# POWER.net
KiCad netlist of a schematic drawn in Altium Designer
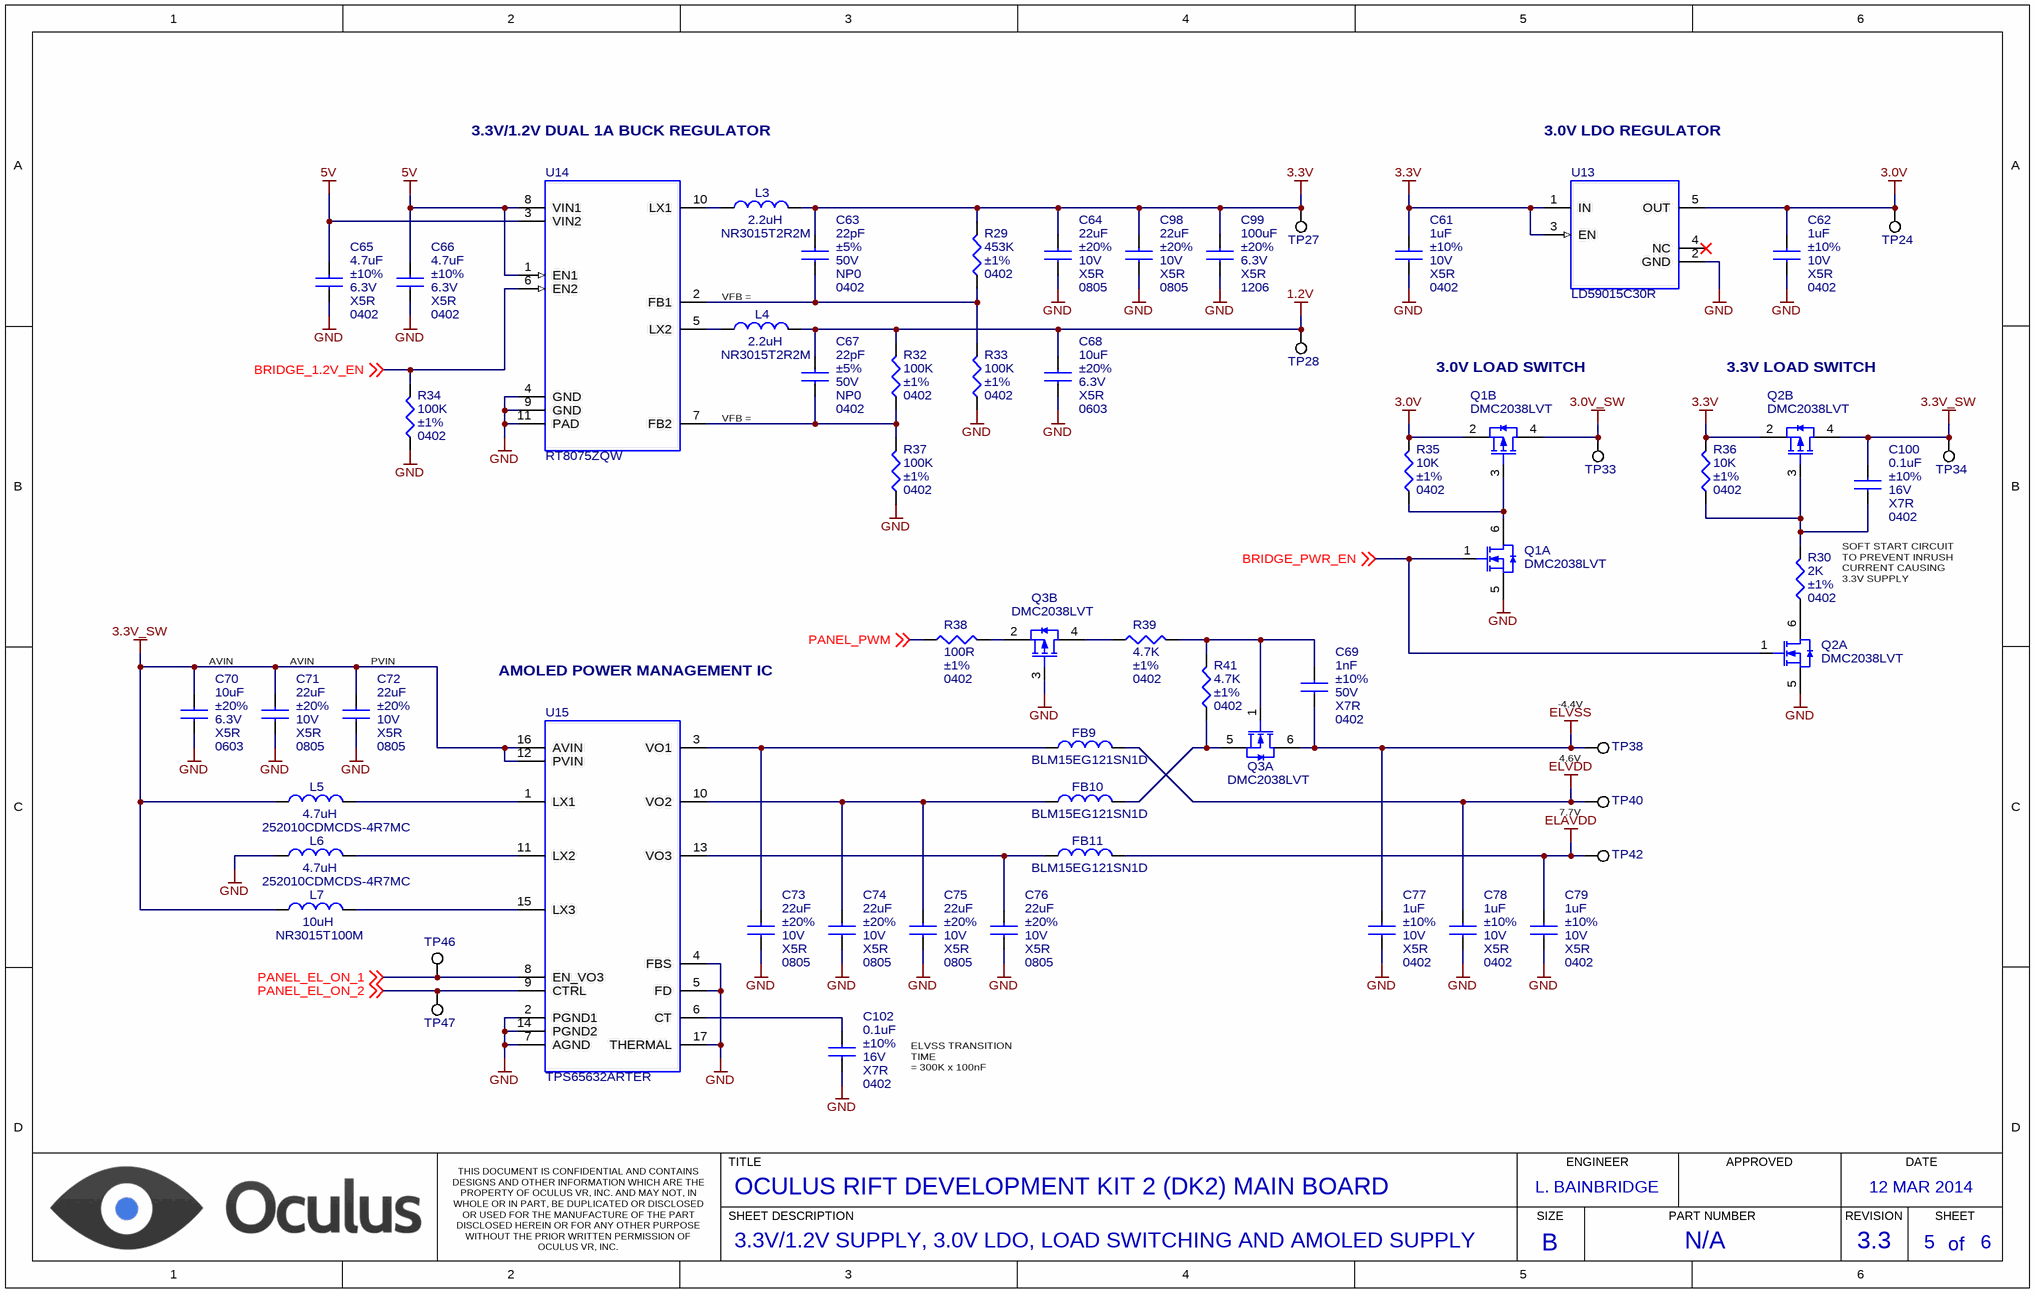
[diagram p0: POWER.SchDoc]

(export (version "E")
  (design (tool "Eeschema 10.0.6"))
  (components
    (comp (ref "C61")
      (value "1uF")
      (footprint "CAP_CERAMIC_0402")
      (description "CAP, CERAMIC, 1uF, ±10%, 10V, X5R, 0402")
      (fields
        (field (name "MANUFACTURER") "MURATA ELECTRONICS")
        (field (name "PART NUMBER") "GRM155R61A105KE15D")
        (field (name "TOLERANCE") "±10%")
        (field (name "VOLTAGE") "10V")
        (field (name "DIELECTRIC") "X5R")
        (field (name "PACKAGE") "0402")
      )
      (libsource (lib "DK2") (part "CAP, CERAMIC"))
    )
    (comp (ref "C62")
      (value "1uF")
      (footprint "CAP_CERAMIC_0402")
      (description "CAP, CERAMIC, 1uF, ±10%, 10V, X5R, 0402")
      (fields
        (field (name "MANUFACTURER") "MURATA ELECTRONICS")
        (field (name "PART NUMBER") "GRM155R61A105KE15D")
        (field (name "TOLERANCE") "±10%")
        (field (name "VOLTAGE") "10V")
        (field (name "DIELECTRIC") "X5R")
        (field (name "PACKAGE") "0402")
      )
      (libsource (lib "DK2") (part "CAP, CERAMIC"))
    )
    (comp (ref "C63")
      (value "22pF")
      (footprint "CAP_CERAMIC_0402")
      (description "CAP, CERAMIC, 22pF, ±5%, 50V, NP0, 0402")
      (fields
        (field (name "MANUFACTURER") "MURATA ELECTRONICS")
        (field (name "PART NUMBER") "GRM1535C1H220JDD5D")
        (field (name "TOLERANCE") "±5%")
        (field (name "VOLTAGE") "50V")
        (field (name "DIELECTRIC") "NP0")
        (field (name "PACKAGE") "0402")
      )
      (libsource (lib "DK2") (part "CAP, CERAMIC"))
    )
    (comp (ref "C64")
      (value "22uF")
      (footprint "CAP_CERAMIC_0805")
      (description "CAP, CERAMIC, 22uF, ±20%, 10V, X5R, 0805")
      (fields
        (field (name "MANUFACTURER") "SAMSUNG")
        (field (name "PART NUMBER") "CL21A226MPQNNNE")
        (field (name "TOLERANCE") "±20%")
        (field (name "VOLTAGE") "10V")
        (field (name "DIELECTRIC") "X5R")
        (field (name "PACKAGE") "0805")
      )
      (libsource (lib "DK2") (part "CAP, CERAMIC"))
    )
    (comp (ref "C65")
      (value "4.7uF")
      (footprint "CAP_CERAMIC_0402")
      (description "CAP, CERAMIC, 4.7uF, ±10%, 6.3V, X5R, 0402")
      (fields
        (field (name "MANUFACTURER") "TDK CORPORATION")
        (field (name "PART NUMBER") "C1005X5R0J475K")
        (field (name "TOLERANCE") "±10%")
        (field (name "VOLTAGE") "6.3V")
        (field (name "DIELECTRIC") "X5R")
        (field (name "PACKAGE") "0402")
      )
      (libsource (lib "DK2") (part "CAP, CERAMIC"))
    )
    (comp (ref "C66")
      (value "4.7uF")
      (footprint "CAP_CERAMIC_0402")
      (description "CAP, CERAMIC, 4.7uF, ±10%, 6.3V, X5R, 0402")
      (fields
        (field (name "MANUFACTURER") "TDK CORPORATION")
        (field (name "PART NUMBER") "C1005X5R0J475K")
        (field (name "TOLERANCE") "±10%")
        (field (name "VOLTAGE") "6.3V")
        (field (name "DIELECTRIC") "X5R")
        (field (name "PACKAGE") "0402")
      )
      (libsource (lib "DK2") (part "CAP, CERAMIC"))
    )
    (comp (ref "C67")
      (value "22pF")
      (footprint "CAP_CERAMIC_0402")
      (description "CAP, CERAMIC, 22pF, ±5%, 50V, NP0, 0402")
      (fields
        (field (name "MANUFACTURER") "MURATA ELECTRONICS")
        (field (name "PART NUMBER") "GRM1535C1H220JDD5D")
        (field (name "TOLERANCE") "±5%")
        (field (name "VOLTAGE") "50V")
        (field (name "DIELECTRIC") "NP0")
        (field (name "PACKAGE") "0402")
      )
      (libsource (lib "DK2") (part "CAP, CERAMIC"))
    )
    (comp (ref "C68")
      (value "10uF")
      (footprint "CAP_CERAMIC_0603")
      (description "CAP, CERAMIC, 10uF, ±20%, 6.3V, X5R, 0603")
      (fields
        (field (name "MANUFACTURER") "MURATA ELECTRONICS")
        (field (name "PART NUMBER") "GRM188R60J106ME47D")
        (field (name "TOLERANCE") "±20%")
        (field (name "VOLTAGE") "6.3V")
        (field (name "DIELECTRIC") "X5R")
        (field (name "PACKAGE") "0603")
      )
      (libsource (lib "DK2") (part "CAP, CERAMIC"))
    )
    (comp (ref "C69")
      (value "1nF")
      (footprint "CAP_CERAMIC_0402")
      (description "CAP, CERAMIC, 1nF, ±10%, 50V, X7R, 0402")
      (fields
        (field (name "MANUFACTURER") "MURATA ELECTRONICS")
        (field (name "PART NUMBER") "GRM155R71H102KA01D")
        (field (name "TOLERANCE") "±10%")
        (field (name "VOLTAGE") "50V")
        (field (name "DIELECTRIC") "X7R")
        (field (name "PACKAGE") "0402")
      )
      (libsource (lib "DK2") (part "CAP, CERAMIC"))
    )
    (comp (ref "C70")
      (value "10uF")
      (footprint "CAP_CERAMIC_0603")
      (description "CAP, CERAMIC, 10uF, ±20%, 6.3V, X5R, 0603")
      (fields
        (field (name "MANUFACTURER") "MURATA ELECTRONICS")
        (field (name "PART NUMBER") "GRM188R60J106ME47D")
        (field (name "TOLERANCE") "±20%")
        (field (name "VOLTAGE") "6.3V")
        (field (name "DIELECTRIC") "X5R")
        (field (name "PACKAGE") "0603")
      )
      (libsource (lib "DK2") (part "CAP, CERAMIC"))
    )
    (comp (ref "C71")
      (value "22uF")
      (footprint "CAP_CERAMIC_0805")
      (description "CAP, CERAMIC, 22uF, ±20%, 10V, X5R, 0805")
      (fields
        (field (name "MANUFACTURER") "SAMSUNG")
        (field (name "PART NUMBER") "CL21A226MPQNNNE")
        (field (name "TOLERANCE") "±20%")
        (field (name "VOLTAGE") "10V")
        (field (name "DIELECTRIC") "X5R")
        (field (name "PACKAGE") "0805")
      )
      (libsource (lib "DK2") (part "CAP, CERAMIC"))
    )
    (comp (ref "C72")
      (value "22uF")
      (footprint "CAP_CERAMIC_0805")
      (description "CAP, CERAMIC, 22uF, ±20%, 10V, X5R, 0805")
      (fields
        (field (name "MANUFACTURER") "SAMSUNG")
        (field (name "PART NUMBER") "CL21A226MPQNNNE")
        (field (name "TOLERANCE") "±20%")
        (field (name "VOLTAGE") "10V")
        (field (name "DIELECTRIC") "X5R")
        (field (name "PACKAGE") "0805")
      )
      (libsource (lib "DK2") (part "CAP, CERAMIC"))
    )
    (comp (ref "C73")
      (value "22uF")
      (footprint "CAP_CERAMIC_0805")
      (description "CAP, CERAMIC, 22uF, ±20%, 10V, X5R, 0805")
      (fields
        (field (name "MANUFACTURER") "SAMSUNG")
        (field (name "PART NUMBER") "CL21A226MPQNNNE")
        (field (name "TOLERANCE") "±20%")
        (field (name "VOLTAGE") "10V")
        (field (name "DIELECTRIC") "X5R")
        (field (name "PACKAGE") "0805")
      )
      (libsource (lib "DK2") (part "CAP, CERAMIC"))
    )
    (comp (ref "C74")
      (value "22uF")
      (footprint "CAP_CERAMIC_0805")
      (description "CAP, CERAMIC, 22uF, ±20%, 10V, X5R, 0805")
      (fields
        (field (name "MANUFACTURER") "SAMSUNG")
        (field (name "PART NUMBER") "CL21A226MPQNNNE")
        (field (name "TOLERANCE") "±20%")
        (field (name "VOLTAGE") "10V")
        (field (name "DIELECTRIC") "X5R")
        (field (name "PACKAGE") "0805")
      )
      (libsource (lib "DK2") (part "CAP, CERAMIC"))
    )
    (comp (ref "C75")
      (value "22uF")
      (footprint "CAP_CERAMIC_0805")
      (description "CAP, CERAMIC, 22uF, ±20%, 10V, X5R, 0805")
      (fields
        (field (name "MANUFACTURER") "SAMSUNG")
        (field (name "PART NUMBER") "CL21A226MPQNNNE")
        (field (name "TOLERANCE") "±20%")
        (field (name "VOLTAGE") "10V")
        (field (name "DIELECTRIC") "X5R")
        (field (name "PACKAGE") "0805")
      )
      (libsource (lib "DK2") (part "CAP, CERAMIC"))
    )
    (comp (ref "C76")
      (value "22uF")
      (footprint "CAP_CERAMIC_0805")
      (description "CAP, CERAMIC, 22uF, ±20%, 10V, X5R, 0805")
      (fields
        (field (name "MANUFACTURER") "SAMSUNG")
        (field (name "PART NUMBER") "CL21A226MPQNNNE")
        (field (name "TOLERANCE") "±20%")
        (field (name "VOLTAGE") "10V")
        (field (name "DIELECTRIC") "X5R")
        (field (name "PACKAGE") "0805")
      )
      (libsource (lib "DK2") (part "CAP, CERAMIC"))
    )
    (comp (ref "C77")
      (value "1uF")
      (footprint "CAP_CERAMIC_0402")
      (description "CAP, CERAMIC, 1uF, ±10%, 10V, X5R, 0402")
      (fields
        (field (name "MANUFACTURER") "MURATA ELECTRONICS")
        (field (name "PART NUMBER") "GRM155R61A105KE15D")
        (field (name "TOLERANCE") "±10%")
        (field (name "VOLTAGE") "10V")
        (field (name "DIELECTRIC") "X5R")
        (field (name "PACKAGE") "0402")
      )
      (libsource (lib "DK2") (part "CAP, CERAMIC"))
    )
    (comp (ref "C78")
      (value "1uF")
      (footprint "CAP_CERAMIC_0402")
      (description "CAP, CERAMIC, 1uF, ±10%, 10V, X5R, 0402")
      (fields
        (field (name "MANUFACTURER") "MURATA ELECTRONICS")
        (field (name "PART NUMBER") "GRM155R61A105KE15D")
        (field (name "TOLERANCE") "±10%")
        (field (name "VOLTAGE") "10V")
        (field (name "DIELECTRIC") "X5R")
        (field (name "PACKAGE") "0402")
      )
      (libsource (lib "DK2") (part "CAP, CERAMIC"))
    )
    (comp (ref "C79")
      (value "1uF")
      (footprint "CAP_CERAMIC_0402")
      (description "CAP, CERAMIC, 1uF, ±10%, 10V, X5R, 0402")
      (fields
        (field (name "MANUFACTURER") "MURATA ELECTRONICS")
        (field (name "PART NUMBER") "GRM155R61A105KE15D")
        (field (name "TOLERANCE") "±10%")
        (field (name "VOLTAGE") "10V")
        (field (name "DIELECTRIC") "X5R")
        (field (name "PACKAGE") "0402")
      )
      (libsource (lib "DK2") (part "CAP, CERAMIC"))
    )
    (comp (ref "C98")
      (value "22uF")
      (footprint "CAP_CERAMIC_0805")
      (description "CAP, CERAMIC, 22uF, ±20%, 10V, X5R, 0805")
      (fields
        (field (name "MANUFACTURER") "SAMSUNG")
        (field (name "PART NUMBER") "CL21A226MPQNNNE")
        (field (name "TOLERANCE") "±20%")
        (field (name "VOLTAGE") "10V")
        (field (name "DIELECTRIC") "X5R")
        (field (name "PACKAGE") "0805")
      )
      (libsource (lib "DK2") (part "CAP, CERAMIC"))
    )
    (comp (ref "C99")
      (value "100uF")
      (footprint "CAP_CERAMIC_1206")
      (description "CAP, CERAMIC, 100uF, ±20%, 6.3V, X5R, 1206")
      (fields
        (field (name "MANUFACTURER") "MURATA ELECTRONICS")
        (field (name "PART NUMBER") "GRM31CR60J107ME39K")
        (field (name "TOLERANCE") "±20%")
        (field (name "VOLTAGE") "6.3V")
        (field (name "DIELECTRIC") "X5R")
        (field (name "PACKAGE") "1206")
      )
      (libsource (lib "DK2") (part "CAP, CERAMIC"))
    )
    (comp (ref "C100")
      (value "0.1uF")
      (footprint "CAP_CERAMIC_0402")
      (description "CAP, CERAMIC, 0.1uF, ±10%, 16V, X7R, 0402")
      (fields
        (field (name "MANUFACTURER") "MURATA ELECTRONICS")
        (field (name "PART NUMBER") "GRM155R71C104KA88D")
        (field (name "TOLERANCE") "±10%")
        (field (name "VOLTAGE") "16V")
        (field (name "DIELECTRIC") "X7R")
        (field (name "PACKAGE") "0402")
      )
      (libsource (lib "DK2") (part "CAP, CERAMIC"))
    )
    (comp (ref "C102")
      (value "0.1uF")
      (footprint "CAP_CERAMIC_0402")
      (description "CAP, CERAMIC, 0.1uF, ±10%, 16V, X7R, 0402")
      (fields
        (field (name "MANUFACTURER") "MURATA ELECTRONICS")
        (field (name "PART NUMBER") "GRM155R71C104KA88D")
        (field (name "TOLERANCE") "±10%")
        (field (name "VOLTAGE") "16V")
        (field (name "DIELECTRIC") "X7R")
        (field (name "PACKAGE") "0402")
      )
      (libsource (lib "DK2") (part "CAP, CERAMIC"))
    )
    (comp (ref "FB9")
      (value "BLM15EG121SN1D")
      (footprint "INDUCTOR_0402")
      (description "FERRITE CHIP BEAD, 120 OHM @ 100MHz, 1.5A, 0402")
      (fields (field (name "MANUFACTURER") "MURATA ELECTRONICS"))
      (libsource (lib "DK2") (part "INDUCTOR"))
    )
    (comp (ref "FB10")
      (value "BLM15EG121SN1D")
      (footprint "INDUCTOR_0402")
      (description "FERRITE CHIP BEAD, 120 OHM @ 100MHz, 1.5A, 0402")
      (fields (field (name "MANUFACTURER") "MURATA ELECTRONICS"))
      (libsource (lib "DK2") (part "INDUCTOR"))
    )
    (comp (ref "FB11")
      (value "BLM15EG121SN1D")
      (footprint "INDUCTOR_0402")
      (description "FERRITE CHIP BEAD, 120 OHM @ 100MHz, 1.5A, 0402")
      (fields (field (name "MANUFACTURER") "MURATA ELECTRONICS"))
      (libsource (lib "DK2") (part "INDUCTOR"))
    )
    (comp (ref "L3")
      (value "2.2uH")
      (footprint "NR3015")
      (description "INDUCTOR, SHIELDED POWER, 2.2uH, 1.5A")
      (fields (field (name "MANUFACTURER") "TAIYO YUDEN") (field (name "PART NUMBER") "NR3015T2R2M"))
      (libsource (lib "") (part "INDUCTOR_1"))
    )
    (comp (ref "L4")
      (value "2.2uH")
      (footprint "NR3015")
      (description "INDUCTOR, SHIELDED POWER, 2.2uH, 1.5A")
      (fields (field (name "MANUFACTURER") "TAIYO YUDEN") (field (name "PART NUMBER") "NR3015T2R2M"))
      (libsource (lib "") (part "INDUCTOR_1"))
    )
    (comp (ref "L5")
      (value "4.7uH")
      (footprint "252010CDMCDS")
      (description "INDUCTOR, SHIELDED POWER, 4.7uH, 1.4A")
      (fields (field (name "MANUFACTURER") "SUMIDA") (field (name "PART NUMBER") "252010CDMCDS-4R7MC"))
      (libsource (lib "") (part "INDUCTOR_1"))
    )
    (comp (ref "L6")
      (value "4.7uH")
      (footprint "252010CDMCDS")
      (description "INDUCTOR, SHIELDED POWER, 4.7uH, 1.4A")
      (fields (field (name "MANUFACTURER") "SUMIDA") (field (name "PART NUMBER") "252010CDMCDS-4R7MC"))
      (libsource (lib "") (part "INDUCTOR_1"))
    )
    (comp (ref "L7")
      (value "10uH")
      (footprint "NR3015")
      (description "INDUCTOR, SHIELDED POWER, 10uH, 730mA")
      (fields (field (name "MANUFACTURER") "TAIYO YUDEN") (field (name "PART NUMBER") "NR3015T100M"))
      (libsource (lib "") (part "INDUCTOR_1"))
    )
    (comp (ref "Q1")
      (value "DMC2038LVT")
      (footprint "TSOT26")
      (description "FET, COMPLEMENTARY, LOGIC LEVEL")
      (fields (field (name "MANUFACTURER") "DIODES INC"))
      (libsource (lib "DK2") (part "DMC2038LVT"))
    )
    (comp (ref "Q2")
      (value "DMC2038LVT")
      (footprint "TSOT26")
      (description "FET, COMPLEMENTARY, LOGIC LEVEL")
      (fields (field (name "MANUFACTURER") "DIODES INC"))
      (libsource (lib "DK2") (part "DMC2038LVT"))
    )
    (comp (ref "Q3")
      (value "DMC2038LVT")
      (footprint "TSOT26")
      (description "FET, COMPLEMENTARY, LOGIC LEVEL")
      (fields (field (name "MANUFACTURER") "DIODES INC"))
      (libsource (lib "DK2") (part "DMC2038LVT"))
    )
    (comp (ref "R29")
      (value "453K")
      (footprint "RESISTOR_0402")
      (description "RES, 453K OHM, 1/10W, ±1%, 0402")
      (fields
        (field (name "MANUFACTURER") "PANASONIC")
        (field (name "PART NUMBER") "ERJ-2RKF4533X")
        (field (name "PACKAGE") "0402")
        (field (name "TOLERANCE") "±1%")
      )
      (libsource (lib "DK2") (part "RESISTOR"))
    )
    (comp (ref "R30")
      (value "2K")
      (footprint "RESISTOR_0402")
      (description "RES, 2K OHM, 1/10W, ±1%, 0402")
      (fields
        (field (name "MANUFACTURER") "PANASONIC")
        (field (name "PART NUMBER") "ERJ-2RKF2001X")
        (field (name "PACKAGE") "0402")
        (field (name "TOLERANCE") "±1%")
      )
      (libsource (lib "DK2") (part "RESISTOR"))
    )
    (comp (ref "R32")
      (value "100K")
      (footprint "RESISTOR_0402")
      (description "RES, 100K OHM, 1/10W, ±1%, 0402")
      (fields
        (field (name "MANUFACTURER") "PANASONIC")
        (field (name "PART NUMBER") "ERJ-2RKF1003X")
        (field (name "PACKAGE") "0402")
        (field (name "TOLERANCE") "±1%")
      )
      (libsource (lib "DK2") (part "RESISTOR"))
    )
    (comp (ref "R33")
      (value "100K")
      (footprint "RESISTOR_0402")
      (description "RES, 100K OHM, 1/10W, ±1%, 0402")
      (fields
        (field (name "MANUFACTURER") "PANASONIC")
        (field (name "PART NUMBER") "ERJ-2RKF1003X")
        (field (name "PACKAGE") "0402")
        (field (name "TOLERANCE") "±1%")
      )
      (libsource (lib "DK2") (part "RESISTOR"))
    )
    (comp (ref "R34")
      (value "100K")
      (footprint "RESISTOR_0402")
      (description "RES, 100K OHM, 1/10W, ±1%, 0402")
      (fields
        (field (name "MANUFACTURER") "PANASONIC")
        (field (name "PART NUMBER") "ERJ-2RKF1003X")
        (field (name "PACKAGE") "0402")
        (field (name "TOLERANCE") "±1%")
      )
      (libsource (lib "DK2") (part "RESISTOR"))
    )
    (comp (ref "R35")
      (value "10K")
      (footprint "RESISTOR_0402")
      (description "RES, 10K OHM, 1/10W, ±1%, 0402")
      (fields
        (field (name "MANUFACTURER") "PANASONIC")
        (field (name "PART NUMBER") "ERJ-2RKF1002X")
        (field (name "PACKAGE") "0402")
        (field (name "TOLERANCE") "±1%")
      )
      (libsource (lib "DK2") (part "RESISTOR"))
    )
    (comp (ref "R36")
      (value "10K")
      (footprint "RESISTOR_0402")
      (description "RES, 10K OHM, 1/10W, ±1%, 0402")
      (fields
        (field (name "MANUFACTURER") "PANASONIC")
        (field (name "PART NUMBER") "ERJ-2RKF1002X")
        (field (name "PACKAGE") "0402")
        (field (name "TOLERANCE") "±1%")
      )
      (libsource (lib "DK2") (part "RESISTOR"))
    )
    (comp (ref "R37")
      (value "100K")
      (footprint "RESISTOR_0402")
      (description "RES, 100K OHM, 1/10W, ±1%, 0402")
      (fields
        (field (name "MANUFACTURER") "PANASONIC")
        (field (name "PART NUMBER") "ERJ-2RKF1003X")
        (field (name "PACKAGE") "0402")
        (field (name "TOLERANCE") "±1%")
      )
      (libsource (lib "DK2") (part "RESISTOR"))
    )
    (comp (ref "R38")
      (value "100R")
      (footprint "RESISTOR_0402")
      (description "RES, 100 OHM, 1/10W, ±1%, 0402")
      (fields
        (field (name "MANUFACTURER") "PANASONIC")
        (field (name "PART NUMBER") "ERJ-2RKF1000X")
        (field (name "PACKAGE") "0402")
        (field (name "TOLERANCE") "±1%")
      )
      (libsource (lib "DK2") (part "RESISTOR"))
    )
    (comp (ref "R39")
      (value "4.7K")
      (footprint "RESISTOR_0402")
      (description "RES, 4.7K OHM, 1/10W, ±1%, 0402")
      (fields
        (field (name "MANUFACTURER") "PANASONIC")
        (field (name "PART NUMBER") "ERJ-2RKF4701X")
        (field (name "PACKAGE") "0402")
        (field (name "TOLERANCE") "±1%")
      )
      (libsource (lib "DK2") (part "RESISTOR"))
    )
    (comp (ref "R41")
      (value "4.7K")
      (footprint "RESISTOR_0402")
      (description "RES, 4.7K OHM, 1/10W, ±1%, 0402")
      (fields
        (field (name "MANUFACTURER") "PANASONIC")
        (field (name "PART NUMBER") "ERJ-2RKF4701X")
        (field (name "PACKAGE") "0402")
        (field (name "TOLERANCE") "±1%")
      )
      (libsource (lib "DK2") (part "RESISTOR"))
    )
    (comp (ref "TP24")
      (value "TEST POINT")
      (footprint "TEST_POINT_PAD_1.2X3MM")
      (libsource (lib "DK2") (part "TEST_POINT_GENERIC"))
    )
    (comp (ref "TP27")
      (value "TEST POINT")
      (footprint "TEST_POINT_PAD_1MM")
      (libsource (lib "DK2") (part "TEST_POINT_GENERIC"))
    )
    (comp (ref "TP28")
      (value "TEST POINT")
      (footprint "TEST_POINT_PAD_1MM")
      (libsource (lib "DK2") (part "TEST_POINT_GENERIC"))
    )
    (comp (ref "TP33")
      (value "TEST POINT")
      (footprint "TEST_POINT_PAD_1MM")
      (libsource (lib "DK2") (part "TEST_POINT_GENERIC"))
    )
    (comp (ref "TP34")
      (value "TEST POINT")
      (footprint "TEST_POINT_PAD_1MM")
      (libsource (lib "DK2") (part "TEST_POINT_GENERIC"))
    )
    (comp (ref "TP38")
      (value "TEST POINT")
      (footprint "TEST_POINT_PAD_1MM")
      (libsource (lib "DK2") (part "TEST_POINT_GENERIC"))
    )
    (comp (ref "TP40")
      (value "TEST POINT")
      (footprint "TEST_POINT_PAD_1MM")
      (libsource (lib "DK2") (part "TEST_POINT_GENERIC"))
    )
    (comp (ref "TP42")
      (value "TEST POINT")
      (footprint "TEST_POINT_PAD_1MM")
      (libsource (lib "DK2") (part "TEST_POINT_GENERIC"))
    )
    (comp (ref "TP46")
      (value "TEST POINT")
      (footprint "TEST_POINT_PAD_1MM")
      (libsource (lib "DK2") (part "TEST_POINT_GENERIC"))
    )
    (comp (ref "TP47")
      (value "TEST POINT")
      (footprint "TEST_POINT_PAD_1MM")
      (libsource (lib "DK2") (part "TEST_POINT_GENERIC"))
    )
    (comp (ref "U13")
      (value "LD59015C30R")
      (footprint "SOT323-5L")
      (description "IC, LDO REGULATOR, 3.0V, 150mA, HIGH PSRR")
      (fields (field (name "MANUFACTURER") "STMICROELECTRONICS"))
      (libsource (lib "DK2") (part "LD59015C30R"))
    )
    (comp (ref "U14")
      (value "RT8075ZQW")
      (footprint "WDFN-10L")
      (description "IC, DUAL STEP DOWN CONVERTER, 1A, 1.25MHz")
      (fields (field (name "MANUFACTURER") "RICHTEK"))
      (libsource (lib "DK2") (part "RT8075ZQW"))
    )
    (comp (ref "U15")
      (value "TPS65632ARTER")
      (footprint "S-PWQFN-N16")
      (description "IC, TRIPLE OUTPUT AMOLED DISPLAY POWER SUPPLY")
      (fields (field (name "MANUFACTURER") "TEXAS INSTRUMENTS"))
      (libsource (lib "DK2") (part "TPS65632ARTER"))
    )
  )
  (nets
    (net (code "1") (name "1.2V") (class "Default")
      (node (ref "C67") (pin "1") (pinfunction "1_1") (pintype "passive"))
      (node (ref "C68") (pin "1") (pinfunction "1_1") (pintype "passive"))
      (node (ref "L4") (pin "1") (pinfunction "1_1") (pintype "passive"))
      (node (ref "R32") (pin "2") (pinfunction "2_2") (pintype "passive"))
      (node (ref "TP28") (pin "1") (pinfunction "1_1") (pintype "passive"))
    )
    (net (code "2") (name "3.0V") (class "Default")
      (node (ref "C62") (pin "1") (pinfunction "1_1") (pintype "passive"))
      (node (ref "Q1") (pin "2") (pinfunction "S_2") (pintype "passive"))
      (node (ref "R35") (pin "2") (pinfunction "2_2") (pintype "passive"))
      (node (ref "TP24") (pin "1") (pinfunction "1_1") (pintype "passive"))
      (node (ref "U13") (pin "5") (pinfunction "OUT_5") (pintype "power_in"))
    )
    (net (code "3") (name "3.0V_SW") (class "Default")
      (node (ref "Q1") (pin "4") (pinfunction "D_4") (pintype "passive"))
      (node (ref "TP33") (pin "1") (pinfunction "1_1") (pintype "passive"))
    )
    (net (code "4") (name "3.3V") (class "Default")
      (node (ref "C61") (pin "1") (pinfunction "1_1") (pintype "passive"))
      (node (ref "C63") (pin "1") (pinfunction "1_1") (pintype "passive"))
      (node (ref "C64") (pin "1") (pinfunction "1_1") (pintype "passive"))
      (node (ref "C98") (pin "1") (pinfunction "1_1") (pintype "passive"))
      (node (ref "C99") (pin "1") (pinfunction "1_1") (pintype "passive"))
      (node (ref "L3") (pin "1") (pinfunction "1_1") (pintype "passive"))
      (node (ref "Q2") (pin "2") (pinfunction "S_2") (pintype "passive"))
      (node (ref "R29") (pin "2") (pinfunction "2_2") (pintype "passive"))
      (node (ref "R36") (pin "2") (pinfunction "2_2") (pintype "passive"))
      (node (ref "TP27") (pin "1") (pinfunction "1_1") (pintype "passive"))
      (node (ref "U13") (pin "1") (pinfunction "IN_1") (pintype "power_in"))
      (node (ref "U13") (pin "3") (pinfunction "EN_3") (pintype "input"))
    )
    (net (code "5") (name "3.3V_SW") (class "Default")
      (node (ref "C100") (pin "1") (pinfunction "1_1") (pintype "passive"))
      (node (ref "C70") (pin "1") (pinfunction "1_1") (pintype "passive"))
      (node (ref "C71") (pin "1") (pinfunction "1_1") (pintype "passive"))
      (node (ref "C72") (pin "1") (pinfunction "1_1") (pintype "passive"))
      (node (ref "L5") (pin "2") (pinfunction "2_2") (pintype "passive"))
      (node (ref "L7") (pin "2") (pinfunction "2_2") (pintype "passive"))
      (node (ref "Q2") (pin "4") (pinfunction "D_4") (pintype "passive"))
      (node (ref "TP34") (pin "1") (pinfunction "1_1") (pintype "passive"))
      (node (ref "U15") (pin "12") (pinfunction "PVIN_12") (pintype "passive"))
      (node (ref "U15") (pin "16") (pinfunction "AVIN_16") (pintype "passive"))
    )
    (net (code "6") (name "5V") (class "Default")
      (node (ref "C65") (pin "1") (pinfunction "1_1") (pintype "passive"))
      (node (ref "C66") (pin "1") (pinfunction "1_1") (pintype "passive"))
      (node (ref "U14") (pin "1") (pinfunction "EN1_1") (pintype "input"))
      (node (ref "U14") (pin "3") (pinfunction "VIN2_3") (pintype "power_in"))
      (node (ref "U14") (pin "8") (pinfunction "VIN1_8") (pintype "power_in"))
    )
    (net (code "7") (name "BRIDGE_1.2V_EN") (class "Default")
      (node (ref "R34") (pin "2") (pinfunction "2_2") (pintype "passive"))
      (node (ref "U14") (pin "6") (pinfunction "EN2_6") (pintype "input"))
    )
    (net (code "8") (name "BRIDGE_PWR_EN") (class "Default")
      (node (ref "Q1") (pin "1") (pinfunction "G_1") (pintype "passive"))
      (node (ref "Q2") (pin "1") (pinfunction "G_1") (pintype "passive"))
    )
    (net (code "9") (name "ELAVDD") (class "Default")
      (node (ref "C79") (pin "1") (pinfunction "1_1") (pintype "passive"))
      (node (ref "FB11") (pin "2") (pinfunction "2_2") (pintype "passive"))
      (node (ref "TP42") (pin "1") (pinfunction "1_1") (pintype "passive"))
    )
    (net (code "10") (name "ELVDD") (class "Default")
      (node (ref "C78") (pin "1") (pinfunction "1_1") (pintype "passive"))
      (node (ref "FB9") (pin "2") (pinfunction "2_2") (pintype "passive"))
      (node (ref "TP40") (pin "1") (pinfunction "1_1") (pintype "passive"))
    )
    (net (code "11") (name "ELVSS") (class "Default")
      (node (ref "C69") (pin "1") (pinfunction "1_1") (pintype "passive"))
      (node (ref "C77") (pin "1") (pinfunction "1_1") (pintype "passive"))
      (node (ref "Q3") (pin "6") (pinfunction "D_6") (pintype "passive"))
      (node (ref "TP38") (pin "1") (pinfunction "1_1") (pintype "passive"))
    )
    (net (code "12") (name "GND") (class "Default")
      (node (ref "C102") (pin "2") (pinfunction "2_2") (pintype "passive"))
      (node (ref "C61") (pin "2") (pinfunction "2_2") (pintype "passive"))
      (node (ref "C62") (pin "2") (pinfunction "2_2") (pintype "passive"))
      (node (ref "C64") (pin "2") (pinfunction "2_2") (pintype "passive"))
      (node (ref "C65") (pin "2") (pinfunction "2_2") (pintype "passive"))
      (node (ref "C66") (pin "2") (pinfunction "2_2") (pintype "passive"))
      (node (ref "C68") (pin "2") (pinfunction "2_2") (pintype "passive"))
      (node (ref "C70") (pin "2") (pinfunction "2_2") (pintype "passive"))
      (node (ref "C71") (pin "2") (pinfunction "2_2") (pintype "passive"))
      (node (ref "C72") (pin "2") (pinfunction "2_2") (pintype "passive"))
      (node (ref "C73") (pin "2") (pinfunction "2_2") (pintype "passive"))
      (node (ref "C74") (pin "2") (pinfunction "2_2") (pintype "passive"))
      (node (ref "C75") (pin "2") (pinfunction "2_2") (pintype "passive"))
      (node (ref "C76") (pin "2") (pinfunction "2_2") (pintype "passive"))
      (node (ref "C77") (pin "2") (pinfunction "2_2") (pintype "passive"))
      (node (ref "C78") (pin "2") (pinfunction "2_2") (pintype "passive"))
      (node (ref "C79") (pin "2") (pinfunction "2_2") (pintype "passive"))
      (node (ref "C98") (pin "2") (pinfunction "2_2") (pintype "passive"))
      (node (ref "C99") (pin "2") (pinfunction "2_2") (pintype "passive"))
      (node (ref "L6") (pin "2") (pinfunction "2_2") (pintype "passive"))
      (node (ref "Q1") (pin "5") (pinfunction "S_5") (pintype "passive"))
      (node (ref "Q2") (pin "5") (pinfunction "S_5") (pintype "passive"))
      (node (ref "Q3") (pin "3") (pinfunction "G_3") (pintype "passive"))
      (node (ref "R33") (pin "1") (pinfunction "1_1") (pintype "passive"))
      (node (ref "R34") (pin "1") (pinfunction "1_1") (pintype "passive"))
      (node (ref "R37") (pin "1") (pinfunction "1_1") (pintype "passive"))
      (node (ref "U13") (pin "2") (pinfunction "GND_2") (pintype "power_in"))
      (node (ref "U14") (pin "11") (pinfunction "PAD_11") (pintype "power_in"))
      (node (ref "U14") (pin "4") (pinfunction "GND_4") (pintype "power_in"))
      (node (ref "U14") (pin "9") (pinfunction "GND_9") (pintype "power_in"))
      (node (ref "U15") (pin "14") (pinfunction "PGND2_14") (pintype "passive"))
      (node (ref "U15") (pin "17") (pinfunction "THERMAL_17") (pintype "passive"))
      (node (ref "U15") (pin "2") (pinfunction "PGND1_2") (pintype "passive"))
      (node (ref "U15") (pin "4") (pinfunction "FBS_4") (pintype "passive"))
      (node (ref "U15") (pin "5") (pinfunction "FD_5") (pintype "passive"))
      (node (ref "U15") (pin "7") (pinfunction "AGND_7") (pintype "passive"))
    )
    (net (code "13") (name "Net-(Q1A-D)") (class "Default")
      (node (ref "Q1") (pin "3") (pinfunction "G_3") (pintype "passive"))
      (node (ref "Q1") (pin "6") (pinfunction "D_6") (pintype "passive"))
      (node (ref "R35") (pin "1") (pinfunction "1_1") (pintype "passive"))
    )
    (net (code "14") (name "Net-(Q2A-D)") (class "Default")
      (node (ref "Q2") (pin "6") (pinfunction "D_6") (pintype "passive"))
      (node (ref "R30") (pin "1") (pinfunction "1_1") (pintype "passive"))
    )
    (net (code "15") (name "Net-(Q2B-G)") (class "Default")
      (node (ref "C100") (pin "2") (pinfunction "2_2") (pintype "passive"))
      (node (ref "Q2") (pin "3") (pinfunction "G_3") (pintype "passive"))
      (node (ref "R30") (pin "2") (pinfunction "2_2") (pintype "passive"))
      (node (ref "R36") (pin "1") (pinfunction "1_1") (pintype "passive"))
    )
    (net (code "16") (name "Net-(Q3A-G)") (class "Default")
      (node (ref "C69") (pin "2") (pinfunction "2_2") (pintype "passive"))
      (node (ref "Q3") (pin "1") (pinfunction "G_1") (pintype "passive"))
      (node (ref "R39") (pin "2") (pinfunction "2_2") (pintype "passive"))
      (node (ref "R41") (pin "2") (pinfunction "2_2") (pintype "passive"))
    )
    (net (code "17") (name "Net-(Q3A-S)") (class "Default")
      (node (ref "FB10") (pin "2") (pinfunction "2_2") (pintype "passive"))
      (node (ref "Q3") (pin "5") (pinfunction "S_5") (pintype "passive"))
      (node (ref "R41") (pin "1") (pinfunction "1_1") (pintype "passive"))
    )
    (net (code "18") (name "Net-(Q3B-D)") (class "Default")
      (node (ref "Q3") (pin "4") (pinfunction "D_4") (pintype "passive"))
      (node (ref "R39") (pin "1") (pinfunction "1_1") (pintype "passive"))
    )
    (net (code "19") (name "Net-(Q3B-S)") (class "Default")
      (node (ref "Q3") (pin "2") (pinfunction "S_2") (pintype "passive"))
      (node (ref "R38") (pin "2") (pinfunction "2_2") (pintype "passive"))
    )
    (net (code "20") (name "Net-(U14-FB1)") (class "Default")
      (node (ref "C63") (pin "2") (pinfunction "2_2") (pintype "passive"))
      (node (ref "R29") (pin "1") (pinfunction "1_1") (pintype "passive"))
      (node (ref "R33") (pin "2") (pinfunction "2_2") (pintype "passive"))
      (node (ref "U14") (pin "2") (pinfunction "FB1_2") (pintype "passive"))
    )
    (net (code "21") (name "Net-(U14-FB2)") (class "Default")
      (node (ref "C67") (pin "2") (pinfunction "2_2") (pintype "passive"))
      (node (ref "R32") (pin "1") (pinfunction "1_1") (pintype "passive"))
      (node (ref "R37") (pin "2") (pinfunction "2_2") (pintype "passive"))
      (node (ref "U14") (pin "7") (pinfunction "FB2_7") (pintype "passive"))
    )
    (net (code "22") (name "Net-(U14-LX1)") (class "Default")
      (node (ref "L3") (pin "2") (pinfunction "2_2") (pintype "passive"))
      (node (ref "U14") (pin "10") (pinfunction "LX1_10") (pintype "power_in"))
    )
    (net (code "23") (name "Net-(U14-LX2)") (class "Default")
      (node (ref "L4") (pin "2") (pinfunction "2_2") (pintype "passive"))
      (node (ref "U14") (pin "5") (pinfunction "LX2_5") (pintype "power_in"))
    )
    (net (code "24") (name "Net-(U15-CT)") (class "Default")
      (node (ref "C102") (pin "1") (pinfunction "1_1") (pintype "passive"))
      (node (ref "U15") (pin "6") (pinfunction "CT_6") (pintype "passive"))
    )
    (net (code "25") (name "Net-(U15-LX1)") (class "Default")
      (node (ref "L5") (pin "1") (pinfunction "1_1") (pintype "passive"))
      (node (ref "U15") (pin "1") (pinfunction "LX1_1") (pintype "passive"))
    )
    (net (code "26") (name "Net-(U15-LX2)") (class "Default")
      (node (ref "L6") (pin "1") (pinfunction "1_1") (pintype "passive"))
      (node (ref "U15") (pin "11") (pinfunction "LX2_11") (pintype "passive"))
    )
    (net (code "27") (name "Net-(U15-LX3)") (class "Default")
      (node (ref "L7") (pin "1") (pinfunction "1_1") (pintype "passive"))
      (node (ref "U15") (pin "15") (pinfunction "LX3_15") (pintype "passive"))
    )
    (net (code "28") (name "Net-(U15-VO1)") (class "Default")
      (node (ref "C73") (pin "1") (pinfunction "1_1") (pintype "passive"))
      (node (ref "FB9") (pin "1") (pinfunction "1_1") (pintype "passive"))
      (node (ref "U15") (pin "3") (pinfunction "VO1_3") (pintype "passive"))
    )
    (net (code "29") (name "Net-(U15-VO2)") (class "Default")
      (node (ref "C74") (pin "1") (pinfunction "1_1") (pintype "passive"))
      (node (ref "C75") (pin "1") (pinfunction "1_1") (pintype "passive"))
      (node (ref "FB10") (pin "1") (pinfunction "1_1") (pintype "passive"))
      (node (ref "U15") (pin "10") (pinfunction "VO2_10") (pintype "passive"))
    )
    (net (code "30") (name "Net-(U15-VO3)") (class "Default")
      (node (ref "C76") (pin "1") (pinfunction "1_1") (pintype "passive"))
      (node (ref "FB11") (pin "1") (pinfunction "1_1") (pintype "passive"))
      (node (ref "U15") (pin "13") (pinfunction "VO3_13") (pintype "passive"))
    )
    (net (code "31") (name "PANEL_EL_ON_1") (class "Default")
      (node (ref "TP46") (pin "1") (pinfunction "1_1") (pintype "passive"))
      (node (ref "U15") (pin "8") (pinfunction "EN_VO3_8") (pintype "passive"))
    )
    (net (code "32") (name "PANEL_EL_ON_2") (class "Default")
      (node (ref "TP47") (pin "1") (pinfunction "1_1") (pintype "passive"))
      (node (ref "U15") (pin "9") (pinfunction "CTRL_9") (pintype "passive"))
    )
    (net (code "33") (name "PANEL_PWM") (class "Default")
      (node (ref "R38") (pin "1") (pinfunction "1_1") (pintype "passive"))
    )
    (net (code "34") (name "unconnected-(U13-NC-Pad4)") (class "Default")
      (node (ref "U13") (pin "4") (pinfunction "NC_4") (pintype "power_in+no_connect"))
    )
  )
)
